# HVAC8New.net
KiCad netlist of a schematic drawn in EAGLE
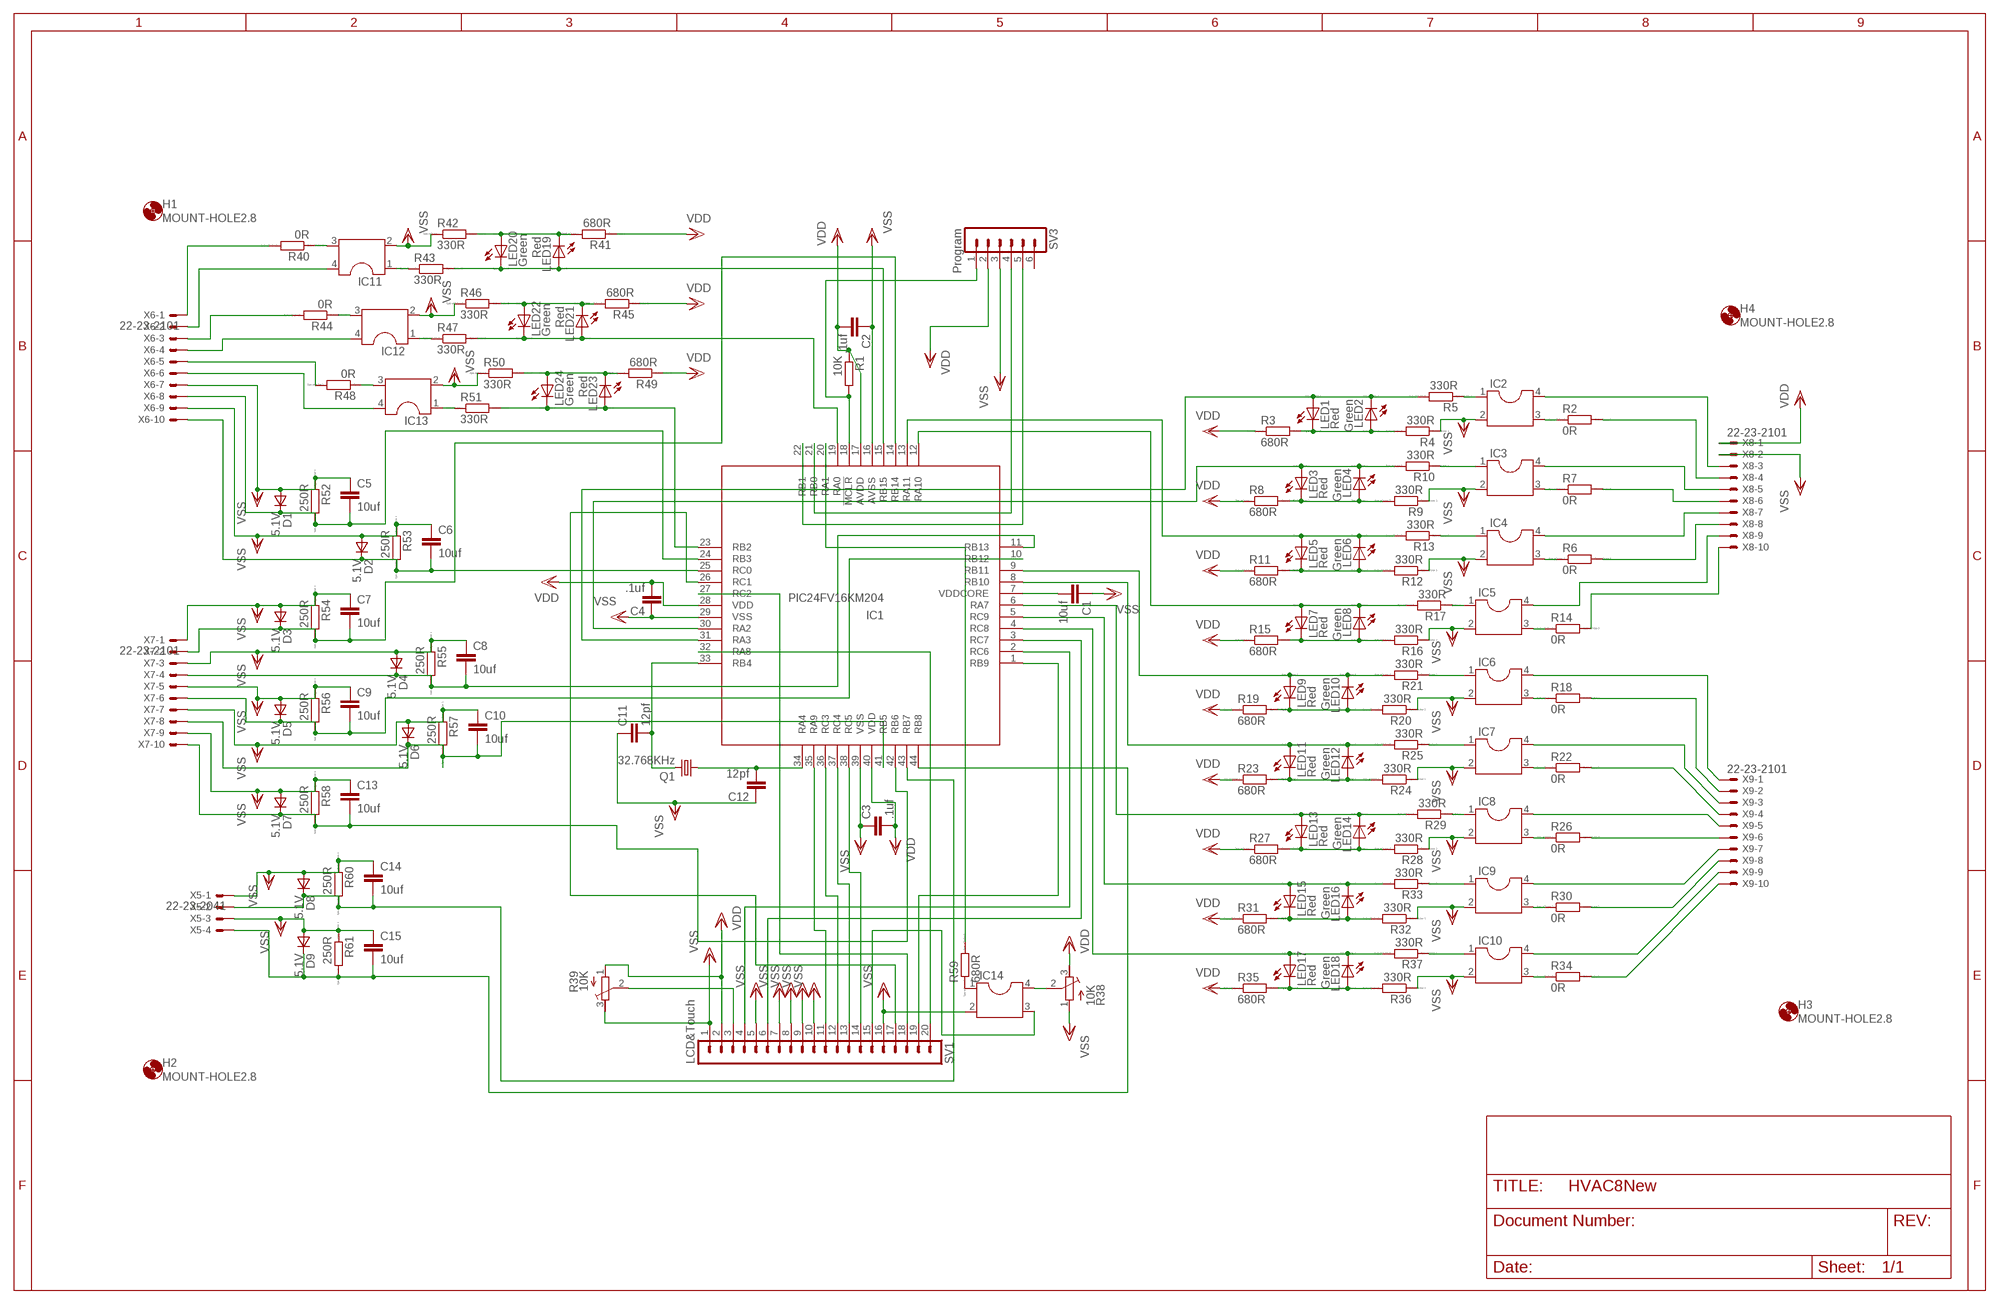
[diagram p0: schematic, sheet 1]

(export (version "E")
  (design (tool "Eeschema 10.0.6"))
  (components
    (comp (ref "C1")
      (value "10uf")
      (footprint "eagle-import:C1206")
      (libsource (lib "eagle-import") (part "C-EUC1206"))
    )
    (comp (ref "C2")
      (value ".1uf")
      (footprint "eagle-import:C1206")
      (libsource (lib "eagle-import") (part "C-EUC1206"))
    )
    (comp (ref "C3")
      (value ".1uf")
      (footprint "eagle-import:C1206")
      (libsource (lib "eagle-import") (part "C-EUC1206"))
    )
    (comp (ref "C4")
      (value ".1uf")
      (footprint "eagle-import:C1206")
      (libsource (lib "eagle-import") (part "C-EUC1206"))
    )
    (comp (ref "C5")
      (value "10uf")
      (footprint "eagle-import:C1206")
      (libsource (lib "eagle-import") (part "C-EUC1206"))
    )
    (comp (ref "C6")
      (value "10uf")
      (footprint "eagle-import:C1206")
      (libsource (lib "eagle-import") (part "C-EUC1206"))
    )
    (comp (ref "C7")
      (value "10uf")
      (footprint "eagle-import:C1206")
      (libsource (lib "eagle-import") (part "C-EUC1206"))
    )
    (comp (ref "C8")
      (value "10uf")
      (footprint "eagle-import:C1206")
      (libsource (lib "eagle-import") (part "C-EUC1206"))
    )
    (comp (ref "C9")
      (value "10uf")
      (footprint "eagle-import:C1206")
      (libsource (lib "eagle-import") (part "C-EUC1206"))
    )
    (comp (ref "C10")
      (value "10uf")
      (footprint "eagle-import:C1206")
      (libsource (lib "eagle-import") (part "C-EUC1206"))
    )
    (comp (ref "C11")
      (value "12pf")
      (footprint "eagle-import:C0603")
      (libsource (lib "eagle-import") (part "C-EUC0603"))
    )
    (comp (ref "C12")
      (value "12pf")
      (footprint "eagle-import:C0603")
      (libsource (lib "eagle-import") (part "C-EUC0603"))
    )
    (comp (ref "C13")
      (value "10uf")
      (footprint "eagle-import:C1206")
      (libsource (lib "eagle-import") (part "C-EUC1206"))
    )
    (comp (ref "C14")
      (value "10uf")
      (footprint "eagle-import:C1206")
      (libsource (lib "eagle-import") (part "C-EUC1206"))
    )
    (comp (ref "C15")
      (value "10uf")
      (footprint "eagle-import:C1206")
      (libsource (lib "eagle-import") (part "C-EUC1206"))
    )
    (comp (ref "D1")
      (value "5.1V")
      (footprint "eagle-import:SOD323")
      (fields (field (name "MPN") "CDSOD323-T05C"))
      (libsource (lib "eagle-import") (part "DSOD323"))
    )
    (comp (ref "D2")
      (value "5.1V")
      (footprint "eagle-import:SOD323")
      (fields (field (name "MPN") "CDSOD323-T05C"))
      (libsource (lib "eagle-import") (part "DSOD323"))
    )
    (comp (ref "D3")
      (value "5.1V")
      (footprint "eagle-import:SOD323")
      (fields (field (name "MPN") "CDSOD323-T05C"))
      (libsource (lib "eagle-import") (part "DSOD323"))
    )
    (comp (ref "D4")
      (value "5.1V")
      (footprint "eagle-import:SOD323")
      (fields (field (name "MPN") "CDSOD323-T05C"))
      (libsource (lib "eagle-import") (part "DSOD323"))
    )
    (comp (ref "D5")
      (value "5.1V")
      (footprint "eagle-import:SOD323")
      (fields (field (name "MPN") "CDSOD323-T05C"))
      (libsource (lib "eagle-import") (part "DSOD323"))
    )
    (comp (ref "D6")
      (value "5.1V")
      (footprint "eagle-import:SOD323")
      (fields (field (name "MPN") "CDSOD323-T05C"))
      (libsource (lib "eagle-import") (part "DSOD323"))
    )
    (comp (ref "D7")
      (value "5.1V")
      (footprint "eagle-import:SOD323")
      (fields (field (name "MPN") "CDSOD323-T05C"))
      (libsource (lib "eagle-import") (part "DSOD323"))
    )
    (comp (ref "D8")
      (value "5.1V")
      (footprint "eagle-import:SOD323")
      (fields (field (name "MPN") "CDSOD323-T05C"))
      (libsource (lib "eagle-import") (part "DSOD323"))
    )
    (comp (ref "D9")
      (value "5.1V")
      (footprint "eagle-import:SOD323")
      (fields (field (name "MPN") "CDSOD323-T05C"))
      (libsource (lib "eagle-import") (part "DSOD323"))
    )
    (comp (ref "H1")
      (value "MOUNT-HOLE2.8")
      (footprint "eagle-import:2,8")
      (libsource (lib "eagle-import") (part "MOUNT-HOLE2.8"))
    )
    (comp (ref "H2")
      (value "MOUNT-HOLE2.8")
      (footprint "eagle-import:2,8")
      (libsource (lib "eagle-import") (part "MOUNT-HOLE2.8"))
    )
    (comp (ref "H3")
      (value "MOUNT-HOLE2.8")
      (footprint "eagle-import:2,8")
      (libsource (lib "eagle-import") (part "MOUNT-HOLE2.8"))
    )
    (comp (ref "H4")
      (value "MOUNT-HOLE2.8")
      (footprint "eagle-import:2,8")
      (libsource (lib "eagle-import") (part "MOUNT-HOLE2.8"))
    )
    (comp (ref "IC1")
      (value "PIC24FV16KM204")
      (footprint "eagle-import:TQFP44")
      (libsource (lib "eagle-import") (part "PIC24FV16KM204"))
    )
    (comp (ref "IC2")
      (value "DIL4S")
      (footprint "eagle-import:SOCKET-04")
      (libsource (lib "eagle-import") (part "DIL4S"))
    )
    (comp (ref "IC3")
      (value "DIL4S")
      (footprint "eagle-import:SOCKET-04")
      (libsource (lib "eagle-import") (part "DIL4S"))
    )
    (comp (ref "IC4")
      (value "DIL4S")
      (footprint "eagle-import:SOCKET-04")
      (libsource (lib "eagle-import") (part "DIL4S"))
    )
    (comp (ref "IC5")
      (value "DIL4S")
      (footprint "eagle-import:SOCKET-04")
      (libsource (lib "eagle-import") (part "DIL4S"))
    )
    (comp (ref "IC6")
      (value "DIL4S")
      (footprint "eagle-import:SOCKET-04")
      (libsource (lib "eagle-import") (part "DIL4S"))
    )
    (comp (ref "IC7")
      (value "DIL4S")
      (footprint "eagle-import:SOCKET-04")
      (libsource (lib "eagle-import") (part "DIL4S"))
    )
    (comp (ref "IC8")
      (value "DIL4S")
      (footprint "eagle-import:SOCKET-04")
      (libsource (lib "eagle-import") (part "DIL4S"))
    )
    (comp (ref "IC9")
      (value "DIL4S")
      (footprint "eagle-import:SOCKET-04")
      (libsource (lib "eagle-import") (part "DIL4S"))
    )
    (comp (ref "IC10")
      (value "DIL4S")
      (footprint "eagle-import:SOCKET-04")
      (libsource (lib "eagle-import") (part "DIL4S"))
    )
    (comp (ref "IC11")
      (value "DIL4S")
      (footprint "eagle-import:SOCKET-04")
      (libsource (lib "eagle-import") (part "DIL4S"))
    )
    (comp (ref "IC12")
      (value "DIL4S")
      (footprint "eagle-import:SOCKET-04")
      (libsource (lib "eagle-import") (part "DIL4S"))
    )
    (comp (ref "IC13")
      (value "DIL4S")
      (footprint "eagle-import:SOCKET-04")
      (libsource (lib "eagle-import") (part "DIL4S"))
    )
    (comp (ref "IC14")
      (value "DIL4S")
      (footprint "eagle-import:SOCKET-04")
      (libsource (lib "eagle-import") (part "DIL4S"))
    )
    (comp (ref "LED1")
      (value "Red")
      (footprint "eagle-import:LED_1206")
      (libsource (lib "eagle-import") (part "LED_E"))
    )
    (comp (ref "LED2")
      (value "Green")
      (footprint "eagle-import:LED_1206")
      (libsource (lib "eagle-import") (part "LED_E"))
    )
    (comp (ref "LED3")
      (value "Red")
      (footprint "eagle-import:LED_1206")
      (libsource (lib "eagle-import") (part "LED_E"))
    )
    (comp (ref "LED4")
      (value "Green")
      (footprint "eagle-import:LED_1206")
      (libsource (lib "eagle-import") (part "LED_E"))
    )
    (comp (ref "LED5")
      (value "Red")
      (footprint "eagle-import:LED_1206")
      (libsource (lib "eagle-import") (part "LED_E"))
    )
    (comp (ref "LED6")
      (value "Green")
      (footprint "eagle-import:LED_1206")
      (libsource (lib "eagle-import") (part "LED_E"))
    )
    (comp (ref "LED7")
      (value "Red")
      (footprint "eagle-import:LED_1206")
      (libsource (lib "eagle-import") (part "LED_E"))
    )
    (comp (ref "LED8")
      (value "Green")
      (footprint "eagle-import:LED_1206")
      (libsource (lib "eagle-import") (part "LED_E"))
    )
    (comp (ref "LED9")
      (value "Red")
      (footprint "eagle-import:LED_1206")
      (libsource (lib "eagle-import") (part "LED_E"))
    )
    (comp (ref "LED10")
      (value "Green")
      (footprint "eagle-import:LED_1206")
      (libsource (lib "eagle-import") (part "LED_E"))
    )
    (comp (ref "LED11")
      (value "Red")
      (footprint "eagle-import:LED_1206")
      (libsource (lib "eagle-import") (part "LED_E"))
    )
    (comp (ref "LED12")
      (value "Green")
      (footprint "eagle-import:LED_1206")
      (libsource (lib "eagle-import") (part "LED_E"))
    )
    (comp (ref "LED13")
      (value "Red")
      (footprint "eagle-import:LED_1206")
      (libsource (lib "eagle-import") (part "LED_E"))
    )
    (comp (ref "LED14")
      (value "Green")
      (footprint "eagle-import:LED_1206")
      (libsource (lib "eagle-import") (part "LED_E"))
    )
    (comp (ref "LED15")
      (value "Red")
      (footprint "eagle-import:LED_1206")
      (libsource (lib "eagle-import") (part "LED_E"))
    )
    (comp (ref "LED16")
      (value "Green")
      (footprint "eagle-import:LED_1206")
      (libsource (lib "eagle-import") (part "LED_E"))
    )
    (comp (ref "LED17")
      (value "Red")
      (footprint "eagle-import:LED_1206")
      (libsource (lib "eagle-import") (part "LED_E"))
    )
    (comp (ref "LED18")
      (value "Green")
      (footprint "eagle-import:LED_1206")
      (libsource (lib "eagle-import") (part "LED_E"))
    )
    (comp (ref "LED19")
      (value "Red")
      (footprint "eagle-import:LED_1206")
      (libsource (lib "eagle-import") (part "LED_E"))
    )
    (comp (ref "LED20")
      (value "Green")
      (footprint "eagle-import:LED_1206")
      (libsource (lib "eagle-import") (part "LED_E"))
    )
    (comp (ref "LED21")
      (value "Red")
      (footprint "eagle-import:LED_1206")
      (libsource (lib "eagle-import") (part "LED_E"))
    )
    (comp (ref "LED22")
      (value "Green")
      (footprint "eagle-import:LED_1206")
      (libsource (lib "eagle-import") (part "LED_E"))
    )
    (comp (ref "LED23")
      (value "Red")
      (footprint "eagle-import:LED_1206")
      (libsource (lib "eagle-import") (part "LED_E"))
    )
    (comp (ref "LED24")
      (value "Green")
      (footprint "eagle-import:LED_1206")
      (libsource (lib "eagle-import") (part "LED_E"))
    )
    (comp (ref "Q1")
      (value "32.768KHz")
      (footprint "eagle-import:TC26H")
      (libsource (lib "eagle-import") (part "CRYSTALTC26H"))
    )
    (comp (ref "R1")
      (value "10K")
      (footprint "eagle-import:R1206")
      (libsource (lib "eagle-import") (part "R-EU_R1206"))
    )
    (comp (ref "R2")
      (value "0R")
      (footprint "eagle-import:R1206")
      (libsource (lib "eagle-import") (part "RR1206"))
    )
    (comp (ref "R3")
      (value "680R")
      (footprint "eagle-import:R1206")
      (libsource (lib "eagle-import") (part "RR1206"))
    )
    (comp (ref "R4")
      (value "330R")
      (footprint "eagle-import:R1206")
      (libsource (lib "eagle-import") (part "RR1206"))
    )
    (comp (ref "R5")
      (value "330R")
      (footprint "eagle-import:R1206")
      (libsource (lib "eagle-import") (part "RR1206"))
    )
    (comp (ref "R6")
      (value "0R")
      (footprint "eagle-import:R1206")
      (libsource (lib "eagle-import") (part "RR1206"))
    )
    (comp (ref "R7")
      (value "0R")
      (footprint "eagle-import:R1206")
      (libsource (lib "eagle-import") (part "RR1206"))
    )
    (comp (ref "R8")
      (value "680R")
      (footprint "eagle-import:R1206")
      (libsource (lib "eagle-import") (part "RR1206"))
    )
    (comp (ref "R9")
      (value "330R")
      (footprint "eagle-import:R1206")
      (libsource (lib "eagle-import") (part "RR1206"))
    )
    (comp (ref "R10")
      (value "330R")
      (footprint "eagle-import:R1206")
      (libsource (lib "eagle-import") (part "RR1206"))
    )
    (comp (ref "R11")
      (value "680R")
      (footprint "eagle-import:R1206")
      (libsource (lib "eagle-import") (part "RR1206"))
    )
    (comp (ref "R12")
      (value "330R")
      (footprint "eagle-import:R1206")
      (libsource (lib "eagle-import") (part "RR1206"))
    )
    (comp (ref "R13")
      (value "330R")
      (footprint "eagle-import:R1206")
      (libsource (lib "eagle-import") (part "RR1206"))
    )
    (comp (ref "R14")
      (value "0R")
      (footprint "eagle-import:R1206")
      (libsource (lib "eagle-import") (part "RR1206"))
    )
    (comp (ref "R15")
      (value "680R")
      (footprint "eagle-import:R1206")
      (libsource (lib "eagle-import") (part "RR1206"))
    )
    (comp (ref "R16")
      (value "330R")
      (footprint "eagle-import:R1206")
      (libsource (lib "eagle-import") (part "RR1206"))
    )
    (comp (ref "R17")
      (value "330R")
      (footprint "eagle-import:R1206")
      (libsource (lib "eagle-import") (part "RR1206"))
    )
    (comp (ref "R18")
      (value "0R")
      (footprint "eagle-import:R1206")
      (libsource (lib "eagle-import") (part "RR1206"))
    )
    (comp (ref "R19")
      (value "680R")
      (footprint "eagle-import:R1206")
      (libsource (lib "eagle-import") (part "RR1206"))
    )
    (comp (ref "R20")
      (value "330R")
      (footprint "eagle-import:R1206")
      (libsource (lib "eagle-import") (part "RR1206"))
    )
    (comp (ref "R21")
      (value "330R")
      (footprint "eagle-import:R1206")
      (libsource (lib "eagle-import") (part "RR1206"))
    )
    (comp (ref "R22")
      (value "0R")
      (footprint "eagle-import:R1206")
      (libsource (lib "eagle-import") (part "RR1206"))
    )
    (comp (ref "R23")
      (value "680R")
      (footprint "eagle-import:R1206")
      (libsource (lib "eagle-import") (part "RR1206"))
    )
    (comp (ref "R24")
      (value "330R")
      (footprint "eagle-import:R1206")
      (libsource (lib "eagle-import") (part "RR1206"))
    )
    (comp (ref "R25")
      (value "330R")
      (footprint "eagle-import:R1206")
      (libsource (lib "eagle-import") (part "RR1206"))
    )
    (comp (ref "R26")
      (value "0R")
      (footprint "eagle-import:R1206")
      (libsource (lib "eagle-import") (part "RR1206"))
    )
    (comp (ref "R27")
      (value "680R")
      (footprint "eagle-import:R1206")
      (libsource (lib "eagle-import") (part "RR1206"))
    )
    (comp (ref "R28")
      (value "330R")
      (footprint "eagle-import:R1206")
      (libsource (lib "eagle-import") (part "RR1206"))
    )
    (comp (ref "R29")
      (value "330R")
      (footprint "eagle-import:R1206")
      (libsource (lib "eagle-import") (part "RR1206"))
    )
    (comp (ref "R30")
      (value "0R")
      (footprint "eagle-import:R1206")
      (libsource (lib "eagle-import") (part "RR1206"))
    )
    (comp (ref "R31")
      (value "680R")
      (footprint "eagle-import:R1206")
      (libsource (lib "eagle-import") (part "RR1206"))
    )
    (comp (ref "R32")
      (value "330R")
      (footprint "eagle-import:R1206")
      (libsource (lib "eagle-import") (part "RR1206"))
    )
    (comp (ref "R33")
      (value "330R")
      (footprint "eagle-import:R1206")
      (libsource (lib "eagle-import") (part "RR1206"))
    )
    (comp (ref "R34")
      (value "0R")
      (footprint "eagle-import:R1206")
      (libsource (lib "eagle-import") (part "RR1206"))
    )
    (comp (ref "R35")
      (value "680R")
      (footprint "eagle-import:R1206")
      (libsource (lib "eagle-import") (part "RR1206"))
    )
    (comp (ref "R36")
      (value "330R")
      (footprint "eagle-import:R1206")
      (libsource (lib "eagle-import") (part "RR1206"))
    )
    (comp (ref "R37")
      (value "330R")
      (footprint "eagle-import:R1206")
      (libsource (lib "eagle-import") (part "RR1206"))
    )
    (comp (ref "R38")
      (value "10K")
      (footprint "eagle-import:RTRIM3296W")
      (libsource (lib "eagle-import") (part "R-TRIMM3296W"))
    )
    (comp (ref "R39")
      (value "10K")
      (footprint "eagle-import:RTRIM3296W")
      (libsource (lib "eagle-import") (part "R-TRIMM3296W"))
    )
    (comp (ref "R40")
      (value "0R")
      (footprint "eagle-import:R1206")
      (libsource (lib "eagle-import") (part "RR1206"))
    )
    (comp (ref "R41")
      (value "680R")
      (footprint "eagle-import:R1206")
      (libsource (lib "eagle-import") (part "RR1206"))
    )
    (comp (ref "R42")
      (value "330R")
      (footprint "eagle-import:R1206")
      (libsource (lib "eagle-import") (part "RR1206"))
    )
    (comp (ref "R43")
      (value "330R")
      (footprint "eagle-import:R1206")
      (libsource (lib "eagle-import") (part "RR1206"))
    )
    (comp (ref "R44")
      (value "0R")
      (footprint "eagle-import:R1206")
      (libsource (lib "eagle-import") (part "RR1206"))
    )
    (comp (ref "R45")
      (value "680R")
      (footprint "eagle-import:R1206")
      (libsource (lib "eagle-import") (part "RR1206"))
    )
    (comp (ref "R46")
      (value "330R")
      (footprint "eagle-import:R1206")
      (libsource (lib "eagle-import") (part "RR1206"))
    )
    (comp (ref "R47")
      (value "330R")
      (footprint "eagle-import:R1206")
      (libsource (lib "eagle-import") (part "RR1206"))
    )
    (comp (ref "R48")
      (value "0R")
      (footprint "eagle-import:R1206")
      (libsource (lib "eagle-import") (part "RR1206"))
    )
    (comp (ref "R49")
      (value "680R")
      (footprint "eagle-import:R1206")
      (libsource (lib "eagle-import") (part "RR1206"))
    )
    (comp (ref "R50")
      (value "330R")
      (footprint "eagle-import:R1206")
      (libsource (lib "eagle-import") (part "RR1206"))
    )
    (comp (ref "R51")
      (value "330R")
      (footprint "eagle-import:R1206")
      (libsource (lib "eagle-import") (part "RR1206"))
    )
    (comp (ref "R52")
      (value "250R")
      (footprint "eagle-import:R1206")
      (libsource (lib "eagle-import") (part "RR1206"))
    )
    (comp (ref "R53")
      (value "250R")
      (footprint "eagle-import:R1206")
      (libsource (lib "eagle-import") (part "RR1206"))
    )
    (comp (ref "R54")
      (value "250R")
      (footprint "eagle-import:R1206")
      (libsource (lib "eagle-import") (part "RR1206"))
    )
    (comp (ref "R55")
      (value "250R")
      (footprint "eagle-import:R1206")
      (libsource (lib "eagle-import") (part "RR1206"))
    )
    (comp (ref "R56")
      (value "250R")
      (footprint "eagle-import:R1206")
      (libsource (lib "eagle-import") (part "RR1206"))
    )
    (comp (ref "R57")
      (value "250R")
      (footprint "eagle-import:R1206")
      (libsource (lib "eagle-import") (part "RR1206"))
    )
    (comp (ref "R58")
      (value "250R")
      (footprint "eagle-import:R1206")
      (libsource (lib "eagle-import") (part "RR1206"))
    )
    (comp (ref "R59")
      (value "680R")
      (footprint "eagle-import:R1206")
      (libsource (lib "eagle-import") (part "RR1206"))
    )
    (comp (ref "R60")
      (value "250R")
      (footprint "eagle-import:R1206")
      (libsource (lib "eagle-import") (part "RR1206"))
    )
    (comp (ref "R61")
      (value "250R")
      (footprint "eagle-import:R1206")
      (libsource (lib "eagle-import") (part "RR1206"))
    )
    (comp (ref "SV1")
      (value "LCD&Touch")
      (footprint "eagle-import:MA20-1")
      (libsource (lib "eagle-import") (part "MA20-1"))
    )
    (comp (ref "SV3")
      (value "Program")
      (footprint "eagle-import:MA06-1")
      (libsource (lib "eagle-import") (part "MA06-1"))
    )
    (comp (ref "X5")
      (value "22-23-2041")
      (footprint "eagle-import:22-23-2041")
      (fields (field (name "MF") "MOLEX"))
      (libsource (lib "eagle-import") (part "22-23-2041"))
    )
    (comp (ref "X6")
      (value "22-23-2101")
      (footprint "eagle-import:22-23-2101")
      (fields (field (name "MF") "MOLEX"))
      (libsource (lib "eagle-import") (part "22-23-2101"))
    )
    (comp (ref "X7")
      (value "22-23-2101")
      (footprint "eagle-import:22-23-2101")
      (fields (field (name "MF") "MOLEX"))
      (libsource (lib "eagle-import") (part "22-23-2101"))
    )
    (comp (ref "X8")
      (value "22-23-2101")
      (footprint "eagle-import:22-23-2101")
      (fields (field (name "MF") "MOLEX"))
      (libsource (lib "eagle-import") (part "22-23-2101"))
    )
    (comp (ref "X9")
      (value "22-23-2101")
      (footprint "eagle-import:22-23-2101")
      (fields (field (name "MF") "MOLEX"))
      (libsource (lib "eagle-import") (part "22-23-2101"))
    )
  )
  (nets
    (net (code "1") (name "Net-(D1-C)") (class "Default")
      (node (ref "C5") (pin "2") (pinfunction "2_2") (pintype "passive"))
      (node (ref "D1") (pin "1") (pinfunction "C_1") (pintype "passive"))
      (node (ref "IC1") (pin "24") (pinfunction "RB3_24") (pintype "bidirectional"))
      (node (ref "R52") (pin "2") (pinfunction "2_2") (pintype "passive"))
      (node (ref "X6") (pin "8") (pinfunction "S_8") (pintype "passive"))
    )
    (net (code "2") (name "Net-(D2-C)") (class "Default")
      (node (ref "C6") (pin "2") (pinfunction "2_2") (pintype "passive"))
      (node (ref "D2") (pin "1") (pinfunction "C_1") (pintype "passive"))
      (node (ref "IC1") (pin "25") (pinfunction "RC0_25") (pintype "bidirectional"))
      (node (ref "R53") (pin "2") (pinfunction "2_2") (pintype "passive"))
      (node (ref "X6") (pin "10") (pinfunction "S_10") (pintype "passive"))
    )
    (net (code "3") (name "Net-(D3-C)") (class "Default")
      (node (ref "C7") (pin "2") (pinfunction "2_2") (pintype "passive"))
      (node (ref "D3") (pin "1") (pinfunction "C_1") (pintype "passive"))
      (node (ref "IC1") (pin "14") (pinfunction "RB14_14") (pintype "bidirectional"))
      (node (ref "R54") (pin "2") (pinfunction "2_2") (pintype "passive"))
      (node (ref "X7") (pin "2") (pinfunction "S_2") (pintype "passive"))
    )
    (net (code "4") (name "Net-(D4-C)") (class "Default")
      (node (ref "C8") (pin "2") (pinfunction "2_2") (pintype "passive"))
      (node (ref "D4") (pin "1") (pinfunction "C_1") (pintype "passive"))
      (node (ref "IC1") (pin "11") (pinfunction "RB13_11") (pintype "bidirectional"))
      (node (ref "R55") (pin "2") (pinfunction "2_2") (pintype "passive"))
      (node (ref "X7") (pin "4") (pinfunction "S_4") (pintype "passive"))
    )
    (net (code "5") (name "Net-(D5-C)") (class "Default")
      (node (ref "C9") (pin "2") (pinfunction "2_2") (pintype "passive"))
      (node (ref "D5") (pin "1") (pinfunction "C_1") (pintype "passive"))
      (node (ref "IC1") (pin "10") (pinfunction "RB12_10") (pintype "bidirectional"))
      (node (ref "R56") (pin "2") (pinfunction "2_2") (pintype "passive"))
      (node (ref "X7") (pin "6") (pinfunction "S_6") (pintype "passive"))
    )
    (net (code "6") (name "Net-(D6-C)") (class "Default")
      (node (ref "C10") (pin "2") (pinfunction "2_2") (pintype "passive"))
      (node (ref "D6") (pin "1") (pinfunction "C_1") (pintype "passive"))
      (node (ref "IC1") (pin "41") (pinfunction "RB5_41") (pintype "bidirectional"))
      (node (ref "R57") (pin "2") (pinfunction "2_2") (pintype "passive"))
      (node (ref "X7") (pin "8") (pinfunction "S_8") (pintype "passive"))
    )
    (net (code "7") (name "Net-(D7-C)") (class "Default")
      (node (ref "C13") (pin "2") (pinfunction "2_2") (pintype "passive"))
      (node (ref "D7") (pin "1") (pinfunction "C_1") (pintype "passive"))
      (node (ref "IC1") (pin "42") (pinfunction "RB6_42") (pintype "bidirectional"))
      (node (ref "R58") (pin "2") (pinfunction "2_2") (pintype "passive"))
      (node (ref "X7") (pin "10") (pinfunction "S_10") (pintype "passive"))
    )
    (net (code "8") (name "Net-(D8-C)") (class "Default")
      (node (ref "C14") (pin "2") (pinfunction "2_2") (pintype "passive"))
      (node (ref "D8") (pin "1") (pinfunction "C_1") (pintype "passive"))
      (node (ref "IC1") (pin "43") (pinfunction "RB7_43") (pintype "bidirectional"))
      (node (ref "R60") (pin "2") (pinfunction "2_2") (pintype "passive"))
      (node (ref "X5") (pin "2") (pinfunction "S_2") (pintype "passive"))
    )
    (net (code "9") (name "Net-(D9-C)") (class "Default")
      (node (ref "C15") (pin "2") (pinfunction "2_2") (pintype "passive"))
      (node (ref "D9") (pin "1") (pinfunction "C_1") (pintype "passive"))
      (node (ref "IC1") (pin "44") (pinfunction "RB8_44") (pintype "bidirectional"))
      (node (ref "R61") (pin "2") (pinfunction "2_2") (pintype "passive"))
      (node (ref "X5") (pin "4") (pinfunction "S_4") (pintype "passive"))
    )
    (net (code "10") (name "Net-(IC1-RA0)") (class "Default")
      (node (ref "IC1") (pin "19") (pinfunction "RA0_19") (pintype "bidirectional"))
      (node (ref "LED21") (pin "A") (pinfunction "A_A") (pintype "passive"))
      (node (ref "LED22") (pin "C") (pinfunction "C_C") (pintype "passive"))
      (node (ref "R47") (pin "2") (pinfunction "2_2") (pintype "passive"))
    )
    (net (code "11") (name "Net-(IC1-RA1)") (class "Default")
      (node (ref "IC1") (pin "20") (pinfunction "RA1_20") (pintype "bidirectional"))
      (node (ref "R59") (pin "2") (pinfunction "2_2") (pintype "passive"))
    )
    (net (code "12") (name "Net-(IC1-RA2)") (class "Default")
      (node (ref "IC1") (pin "30") (pinfunction "RA2_30") (pintype "bidirectional"))
      (node (ref "LED3") (pin "A") (pinfunction "A_A") (pintype "passive"))
      (node (ref "LED4") (pin "C") (pinfunction "C_C") (pintype "passive"))
      (node (ref "R10") (pin "2") (pinfunction "2_2") (pintype "passive"))
    )
    (net (code "13") (name "Net-(IC1-RA3)") (class "Default")
      (node (ref "IC1") (pin "31") (pinfunction "RA3_31") (pintype "bidirectional"))
      (node (ref "LED1") (pin "A") (pinfunction "A_A") (pintype "passive"))
      (node (ref "LED2") (pin "C") (pinfunction "C_C") (pintype "passive"))
      (node (ref "R5") (pin "2") (pinfunction "2_2") (pintype "passive"))
    )
    (net (code "14") (name "Net-(IC1-RA4)") (class "Default")
      (node (ref "C12") (pin "2") (pinfunction "2_2") (pintype "passive"))
      (node (ref "IC1") (pin "34") (pinfunction "RA4_34") (pintype "bidirectional"))
      (node (ref "Q1") (pin "1") (pinfunction "1_1") (pintype "passive"))
    )
    (net (code "15") (name "Net-(IC1-RA7)") (class "Default")
      (node (ref "IC1") (pin "6") (pinfunction "RA7_6") (pintype "bidirectional"))
      (node (ref "LED13") (pin "A") (pinfunction "A_A") (pintype "passive"))
      (node (ref "LED14") (pin "C") (pinfunction "C_C") (pintype "passive"))
      (node (ref "R29") (pin "2") (pinfunction "2_2") (pintype "passive"))
    )
    (net (code "16") (name "Net-(IC1-RA8)") (class "Default")
      (node (ref "IC1") (pin "32") (pinfunction "RA8_32") (pintype "bidirectional"))
      (node (ref "SV1") (pin "20") (pinfunction "20_20") (pintype "passive"))
    )
    (net (code "17") (name "Net-(IC1-RA9)") (class "Default")
      (node (ref "IC1") (pin "35") (pinfunction "RA9_35") (pintype "bidirectional"))
      (node (ref "SV1") (pin "11") (pinfunction "11_11") (pintype "passive"))
    )
    (net (code "18") (name "Net-(IC1-RA10)") (class "Default")
      (node (ref "IC1") (pin "12") (pinfunction "RA10_12") (pintype "bidirectional"))
      (node (ref "LED7") (pin "A") (pinfunction "A_A") (pintype "passive"))
      (node (ref "LED8") (pin "C") (pinfunction "C_C") (pintype "passive"))
      (node (ref "R17") (pin "2") (pinfunction "2_2") (pintype "passive"))
    )
    (net (code "19") (name "Net-(IC1-RA11)") (class "Default")
      (node (ref "IC1") (pin "13") (pinfunction "RA11_13") (pintype "bidirectional"))
      (node (ref "LED5") (pin "A") (pinfunction "A_A") (pintype "passive"))
      (node (ref "LED6") (pin "C") (pinfunction "C_C") (pintype "passive"))
      (node (ref "R13") (pin "2") (pinfunction "2_2") (pintype "passive"))
    )
    (net (code "20") (name "Net-(IC1-RB0)") (class "Default")
      (node (ref "IC1") (pin "21") (pinfunction "RB0_21") (pintype "bidirectional"))
      (node (ref "SV3") (pin "4") (pinfunction "4_4") (pintype "passive"))
    )
    (net (code "21") (name "Net-(IC1-RB1)") (class "Default")
      (node (ref "IC1") (pin "22") (pinfunction "RB1_22") (pintype "bidirectional"))
      (node (ref "SV3") (pin "5") (pinfunction "5_5") (pintype "passive"))
    )
    (net (code "22") (name "Net-(IC1-RB2)") (class "Default")
      (node (ref "IC1") (pin "23") (pinfunction "RB2_23") (pintype "bidirectional"))
      (node (ref "LED23") (pin "A") (pinfunction "A_A") (pintype "passive"))
      (node (ref "LED24") (pin "C") (pinfunction "C_C") (pintype "passive"))
      (node (ref "R51") (pin "2") (pinfunction "2_2") (pintype "passive"))
    )
    (net (code "23") (name "Net-(IC1-RB4)") (class "Default")
      (node (ref "C11") (pin "2") (pinfunction "2_2") (pintype "passive"))
      (node (ref "IC1") (pin "33") (pinfunction "RB4_33") (pintype "bidirectional"))
      (node (ref "Q1") (pin "2") (pinfunction "2_2") (pintype "passive"))
    )
    (net (code "24") (name "Net-(IC1-RB9)") (class "Default")
      (node (ref "IC1") (pin "1") (pinfunction "RB9_1") (pintype "bidirectional"))
      (node (ref "SV1") (pin "19") (pinfunction "19_19") (pintype "passive"))
    )
    (net (code "25") (name "Net-(IC1-RB10)") (class "Default")
      (node (ref "IC1") (pin "8") (pinfunction "RB10_8") (pintype "bidirectional"))
      (node (ref "LED11") (pin "A") (pinfunction "A_A") (pintype "passive"))
      (node (ref "LED12") (pin "C") (pinfunction "C_C") (pintype "passive"))
      (node (ref "R25") (pin "2") (pinfunction "2_2") (pintype "passive"))
    )
    (net (code "26") (name "Net-(IC1-RB11)") (class "Default")
      (node (ref "IC1") (pin "9") (pinfunction "RB11_9") (pintype "bidirectional"))
      (node (ref "LED10") (pin "C") (pinfunction "C_C") (pintype "passive"))
      (node (ref "LED9") (pin "A") (pinfunction "A_A") (pintype "passive"))
      (node (ref "R21") (pin "2") (pinfunction "2_2") (pintype "passive"))
    )
    (net (code "27") (name "Net-(IC1-RB15)") (class "Default")
      (node (ref "IC1") (pin "15") (pinfunction "RB15_15") (pintype "bidirectional"))
      (node (ref "LED19") (pin "A") (pinfunction "A_A") (pintype "passive"))
      (node (ref "LED20") (pin "C") (pinfunction "C_C") (pintype "passive"))
      (node (ref "R43") (pin "2") (pinfunction "2_2") (pintype "passive"))
    )
    (net (code "28") (name "Net-(IC1-RC1)") (class "Default")
      (node (ref "IC1") (pin "26") (pinfunction "RC1_26") (pintype "bidirectional"))
      (node (ref "SV1") (pin "17") (pinfunction "17_17") (pintype "passive"))
    )
    (net (code "29") (name "Net-(IC1-RC2)") (class "Default")
      (node (ref "IC1") (pin "27") (pinfunction "RC2_27") (pintype "bidirectional"))
      (node (ref "SV1") (pin "18") (pinfunction "18_18") (pintype "passive"))
    )
    (net (code "30") (name "Net-(IC1-RC3)") (class "Default")
      (node (ref "IC1") (pin "36") (pinfunction "RC3_36") (pintype "bidirectional"))
      (node (ref "SV1") (pin "12") (pinfunction "12_12") (pintype "passive"))
    )
    (net (code "31") (name "Net-(IC1-RC4)") (class "Default")
      (node (ref "IC1") (pin "37") (pinfunction "RC4_37") (pintype "bidirectional"))
      (node (ref "SV1") (pin "13") (pinfunction "13_13") (pintype "passive"))
    )
    (net (code "32") (name "Net-(IC1-RC5)") (class "Default")
      (node (ref "IC1") (pin "38") (pinfunction "RC5_38") (pintype "bidirectional"))
      (node (ref "SV1") (pin "14") (pinfunction "14_14") (pintype "passive"))
    )
    (net (code "33") (name "Net-(IC1-RC6)") (class "Default")
      (node (ref "IC1") (pin "2") (pinfunction "RC6_2") (pintype "bidirectional"))
      (node (ref "SV1") (pin "4") (pinfunction "4_4") (pintype "passive"))
    )
    (net (code "34") (name "Net-(IC1-RC7)") (class "Default")
      (node (ref "IC1") (pin "3") (pinfunction "RC7_3") (pintype "bidirectional"))
      (node (ref "SV1") (pin "6") (pinfunction "6_6") (pintype "passive"))
    )
    (net (code "35") (name "Net-(IC1-RC8)") (class "Default")
      (node (ref "IC1") (pin "4") (pinfunction "RC8_4") (pintype "bidirectional"))
      (node (ref "LED17") (pin "A") (pinfunction "A_A") (pintype "passive"))
      (node (ref "LED18") (pin "C") (pinfunction "C_C") (pintype "passive"))
      (node (ref "R37") (pin "2") (pinfunction "2_2") (pintype "passive"))
    )
    (net (code "36") (name "Net-(IC1-RC9)") (class "Default")
      (node (ref "IC1") (pin "5") (pinfunction "RC9_5") (pintype "bidirectional"))
      (node (ref "LED15") (pin "A") (pinfunction "A_A") (pintype "passive"))
      (node (ref "LED16") (pin "C") (pinfunction "C_C") (pintype "passive"))
      (node (ref "R33") (pin "2") (pinfunction "2_2") (pintype "passive"))
    )
    (net (code "37") (name "Net-(IC1-VDDCORE)") (class "Default")
      (node (ref "C1") (pin "2") (pinfunction "2_2") (pintype "passive"))
      (node (ref "IC1") (pin "7") (pinfunction "VDDCORE_7") (pintype "power_in"))
    )
    (net (code "38") (name "Net-(IC1-~{MCLR})") (class "Default")
      (node (ref "IC1") (pin "18") (pinfunction "~{MCLR}_18") (pintype "bidirectional"))
      (node (ref "R1") (pin "2") (pinfunction "2_2") (pintype "passive"))
      (node (ref "SV3") (pin "1") (pinfunction "1_1") (pintype "passive"))
    )
    (net (code "39") (name "Net-(IC2-Pad1)") (class "Default")
      (node (ref "IC2") (pin "1") (pinfunction "1_1") (pintype "passive"))
      (node (ref "R5") (pin "1") (pinfunction "1_1") (pintype "passive"))
    )
    (net (code "40") (name "Net-(IC2-Pad3)") (class "Default")
      (node (ref "IC2") (pin "3") (pinfunction "3_3") (pintype "passive"))
      (node (ref "R2") (pin "1") (pinfunction "1_1") (pintype "passive"))
    )
    (net (code "41") (name "Net-(IC3-Pad1)") (class "Default")
      (node (ref "IC3") (pin "1") (pinfunction "1_1") (pintype "passive"))
      (node (ref "R10") (pin "1") (pinfunction "1_1") (pintype "passive"))
    )
    (net (code "42") (name "Net-(IC3-Pad3)") (class "Default")
      (node (ref "IC3") (pin "3") (pinfunction "3_3") (pintype "passive"))
      (node (ref "R7") (pin "1") (pinfunction "1_1") (pintype "passive"))
    )
    (net (code "43") (name "Net-(IC4-Pad1)") (class "Default")
      (node (ref "IC4") (pin "1") (pinfunction "1_1") (pintype "passive"))
      (node (ref "R13") (pin "1") (pinfunction "1_1") (pintype "passive"))
    )
    (net (code "44") (name "Net-(IC4-Pad3)") (class "Default")
      (node (ref "IC4") (pin "3") (pinfunction "3_3") (pintype "passive"))
      (node (ref "R6") (pin "1") (pinfunction "1_1") (pintype "passive"))
    )
    (net (code "45") (name "Net-(IC5-Pad1)") (class "Default")
      (node (ref "IC5") (pin "1") (pinfunction "1_1") (pintype "passive"))
      (node (ref "R17") (pin "1") (pinfunction "1_1") (pintype "passive"))
    )
    (net (code "46") (name "Net-(IC5-Pad3)") (class "Default")
      (node (ref "IC5") (pin "3") (pinfunction "3_3") (pintype "passive"))
      (node (ref "R14") (pin "1") (pinfunction "1_1") (pintype "passive"))
    )
    (net (code "47") (name "Net-(IC6-Pad1)") (class "Default")
      (node (ref "IC6") (pin "1") (pinfunction "1_1") (pintype "passive"))
      (node (ref "R21") (pin "1") (pinfunction "1_1") (pintype "passive"))
    )
    (net (code "48") (name "Net-(IC6-Pad3)") (class "Default")
      (node (ref "IC6") (pin "3") (pinfunction "3_3") (pintype "passive"))
      (node (ref "R18") (pin "1") (pinfunction "1_1") (pintype "passive"))
    )
    (net (code "49") (name "Net-(IC7-Pad1)") (class "Default")
      (node (ref "IC7") (pin "1") (pinfunction "1_1") (pintype "passive"))
      (node (ref "R25") (pin "1") (pinfunction "1_1") (pintype "passive"))
    )
    (net (code "50") (name "Net-(IC7-Pad3)") (class "Default")
      (node (ref "IC7") (pin "3") (pinfunction "3_3") (pintype "passive"))
      (node (ref "R22") (pin "1") (pinfunction "1_1") (pintype "passive"))
    )
    (net (code "51") (name "Net-(IC8-Pad1)") (class "Default")
      (node (ref "IC8") (pin "1") (pinfunction "1_1") (pintype "passive"))
      (node (ref "R29") (pin "1") (pinfunction "1_1") (pintype "passive"))
    )
    (net (code "52") (name "Net-(IC8-Pad3)") (class "Default")
      (node (ref "IC8") (pin "3") (pinfunction "3_3") (pintype "passive"))
      (node (ref "R26") (pin "1") (pinfunction "1_1") (pintype "passive"))
    )
    (net (code "53") (name "Net-(IC9-Pad1)") (class "Default")
      (node (ref "IC9") (pin "1") (pinfunction "1_1") (pintype "passive"))
      (node (ref "R33") (pin "1") (pinfunction "1_1") (pintype "passive"))
    )
    (net (code "54") (name "Net-(IC9-Pad3)") (class "Default")
      (node (ref "IC9") (pin "3") (pinfunction "3_3") (pintype "passive"))
      (node (ref "R30") (pin "1") (pinfunction "1_1") (pintype "passive"))
    )
    (net (code "55") (name "Net-(IC10-Pad1)") (class "Default")
      (node (ref "IC10") (pin "1") (pinfunction "1_1") (pintype "passive"))
      (node (ref "R37") (pin "1") (pinfunction "1_1") (pintype "passive"))
    )
    (net (code "56") (name "Net-(IC10-Pad3)") (class "Default")
      (node (ref "IC10") (pin "3") (pinfunction "3_3") (pintype "passive"))
      (node (ref "R34") (pin "1") (pinfunction "1_1") (pintype "passive"))
    )
    (net (code "57") (name "Net-(IC11-Pad1)") (class "Default")
      (node (ref "IC11") (pin "1") (pinfunction "1_1") (pintype "passive"))
      (node (ref "R43") (pin "1") (pinfunction "1_1") (pintype "passive"))
    )
    (net (code "58") (name "Net-(IC11-Pad3)") (class "Default")
      (node (ref "IC11") (pin "3") (pinfunction "3_3") (pintype "passive"))
      (node (ref "R40") (pin "1") (pinfunction "1_1") (pintype "passive"))
    )
    (net (code "59") (name "Net-(IC12-Pad1)") (class "Default")
      (node (ref "IC12") (pin "1") (pinfunction "1_1") (pintype "passive"))
      (node (ref "R47") (pin "1") (pinfunction "1_1") (pintype "passive"))
    )
    (net (code "60") (name "Net-(IC12-Pad3)") (class "Default")
      (node (ref "IC12") (pin "3") (pinfunction "3_3") (pintype "passive"))
      (node (ref "R44") (pin "1") (pinfunction "1_1") (pintype "passive"))
    )
    (net (code "61") (name "Net-(IC13-Pad1)") (class "Default")
      (node (ref "IC13") (pin "1") (pinfunction "1_1") (pintype "passive"))
      (node (ref "R51") (pin "1") (pinfunction "1_1") (pintype "passive"))
    )
    (net (code "62") (name "Net-(IC13-Pad3)") (class "Default")
      (node (ref "IC13") (pin "3") (pinfunction "3_3") (pintype "passive"))
      (node (ref "R48") (pin "1") (pinfunction "1_1") (pintype "passive"))
    )
    (net (code "63") (name "Net-(IC14-Pad1)") (class "Default")
      (node (ref "IC14") (pin "1") (pinfunction "1_1") (pintype "passive"))
      (node (ref "R59") (pin "1") (pinfunction "1_1") (pintype "passive"))
    )
    (net (code "64") (name "Net-(IC14-Pad3)") (class "Default")
      (node (ref "IC14") (pin "3") (pinfunction "3_3") (pintype "passive"))
      (node (ref "SV1") (pin "15") (pinfunction "15_15") (pintype "passive"))
    )
    (net (code "65") (name "Net-(LED1-PadC)") (class "Default")
      (node (ref "LED1") (pin "C") (pinfunction "C_C") (pintype "passive"))
      (node (ref "LED2") (pin "A") (pinfunction "A_A") (pintype "passive"))
      (node (ref "R3") (pin "2") (pinfunction "2_2") (pintype "passive"))
      (node (ref "R4") (pin "2") (pinfunction "2_2") (pintype "passive"))
    )
    (net (code "66") (name "Net-(LED3-PadC)") (class "Default")
      (node (ref "LED3") (pin "C") (pinfunction "C_C") (pintype "passive"))
      (node (ref "LED4") (pin "A") (pinfunction "A_A") (pintype "passive"))
      (node (ref "R8") (pin "2") (pinfunction "2_2") (pintype "passive"))
      (node (ref "R9") (pin "2") (pinfunction "2_2") (pintype "passive"))
    )
    (net (code "67") (name "Net-(LED5-PadC)") (class "Default")
      (node (ref "LED5") (pin "C") (pinfunction "C_C") (pintype "passive"))
      (node (ref "LED6") (pin "A") (pinfunction "A_A") (pintype "passive"))
      (node (ref "R11") (pin "2") (pinfunction "2_2") (pintype "passive"))
      (node (ref "R12") (pin "2") (pinfunction "2_2") (pintype "passive"))
    )
    (net (code "68") (name "Net-(LED7-PadC)") (class "Default")
      (node (ref "LED7") (pin "C") (pinfunction "C_C") (pintype "passive"))
      (node (ref "LED8") (pin "A") (pinfunction "A_A") (pintype "passive"))
      (node (ref "R15") (pin "2") (pinfunction "2_2") (pintype "passive"))
      (node (ref "R16") (pin "2") (pinfunction "2_2") (pintype "passive"))
    )
    (net (code "69") (name "Net-(LED10-PadA)") (class "Default")
      (node (ref "LED10") (pin "A") (pinfunction "A_A") (pintype "passive"))
      (node (ref "LED9") (pin "C") (pinfunction "C_C") (pintype "passive"))
      (node (ref "R19") (pin "2") (pinfunction "2_2") (pintype "passive"))
      (node (ref "R20") (pin "2") (pinfunction "2_2") (pintype "passive"))
    )
    (net (code "70") (name "Net-(LED11-PadC)") (class "Default")
      (node (ref "LED11") (pin "C") (pinfunction "C_C") (pintype "passive"))
      (node (ref "LED12") (pin "A") (pinfunction "A_A") (pintype "passive"))
      (node (ref "R23") (pin "2") (pinfunction "2_2") (pintype "passive"))
      (node (ref "R24") (pin "2") (pinfunction "2_2") (pintype "passive"))
    )
    (net (code "71") (name "Net-(LED13-PadC)") (class "Default")
      (node (ref "LED13") (pin "C") (pinfunction "C_C") (pintype "passive"))
      (node (ref "LED14") (pin "A") (pinfunction "A_A") (pintype "passive"))
      (node (ref "R27") (pin "2") (pinfunction "2_2") (pintype "passive"))
      (node (ref "R28") (pin "2") (pinfunction "2_2") (pintype "passive"))
    )
    (net (code "72") (name "Net-(LED15-PadC)") (class "Default")
      (node (ref "LED15") (pin "C") (pinfunction "C_C") (pintype "passive"))
      (node (ref "LED16") (pin "A") (pinfunction "A_A") (pintype "passive"))
      (node (ref "R31") (pin "2") (pinfunction "2_2") (pintype "passive"))
      (node (ref "R32") (pin "2") (pinfunction "2_2") (pintype "passive"))
    )
    (net (code "73") (name "Net-(LED17-PadC)") (class "Default")
      (node (ref "LED17") (pin "C") (pinfunction "C_C") (pintype "passive"))
      (node (ref "LED18") (pin "A") (pinfunction "A_A") (pintype "passive"))
      (node (ref "R35") (pin "2") (pinfunction "2_2") (pintype "passive"))
      (node (ref "R36") (pin "2") (pinfunction "2_2") (pintype "passive"))
    )
    (net (code "74") (name "Net-(LED19-PadC)") (class "Default")
      (node (ref "LED19") (pin "C") (pinfunction "C_C") (pintype "passive"))
      (node (ref "LED20") (pin "A") (pinfunction "A_A") (pintype "passive"))
      (node (ref "R41") (pin "2") (pinfunction "2_2") (pintype "passive"))
      (node (ref "R42") (pin "2") (pinfunction "2_2") (pintype "passive"))
    )
    (net (code "75") (name "Net-(LED21-PadC)") (class "Default")
      (node (ref "LED21") (pin "C") (pinfunction "C_C") (pintype "passive"))
      (node (ref "LED22") (pin "A") (pinfunction "A_A") (pintype "passive"))
      (node (ref "R45") (pin "2") (pinfunction "2_2") (pintype "passive"))
      (node (ref "R46") (pin "2") (pinfunction "2_2") (pintype "passive"))
    )
    (net (code "76") (name "Net-(LED23-PadC)") (class "Default")
      (node (ref "LED23") (pin "C") (pinfunction "C_C") (pintype "passive"))
      (node (ref "LED24") (pin "A") (pinfunction "A_A") (pintype "passive"))
      (node (ref "R49") (pin "2") (pinfunction "2_2") (pintype "passive"))
      (node (ref "R50") (pin "2") (pinfunction "2_2") (pintype "passive"))
    )
    (net (code "77") (name "Net-(R38-S)") (class "Default")
      (node (ref "IC14") (pin "4") (pinfunction "4_4") (pintype "passive"))
      (node (ref "R38") (pin "2") (pinfunction "S_2") (pintype "passive"))
    )
    (net (code "78") (name "Net-(R39-S)") (class "Default")
      (node (ref "R39") (pin "2") (pinfunction "S_2") (pintype "passive"))
      (node (ref "SV1") (pin "3") (pinfunction "3_3") (pintype "passive"))
    )
    (net (code "79") (name "Net-(X6A-S)") (class "Default")
      (node (ref "R40") (pin "2") (pinfunction "2_2") (pintype "passive"))
      (node (ref "X6") (pin "1") (pinfunction "S_1") (pintype "passive"))
    )
    (net (code "80") (name "Net-(X6C-S)") (class "Default")
      (node (ref "IC11") (pin "4") (pinfunction "4_4") (pintype "passive"))
      (node (ref "X6") (pin "2") (pinfunction "S_2") (pintype "passive"))
    )
    (net (code "81") (name "Net-(X6D-S)") (class "Default")
      (node (ref "R44") (pin "2") (pinfunction "2_2") (pintype "passive"))
      (node (ref "X6") (pin "3") (pinfunction "S_3") (pintype "passive"))
    )
    (net (code "82") (name "Net-(X6E-S)") (class "Default")
      (node (ref "IC12") (pin "4") (pinfunction "4_4") (pintype "passive"))
      (node (ref "X6") (pin "4") (pinfunction "S_4") (pintype "passive"))
    )
    (net (code "83") (name "Net-(X6F-S)") (class "Default")
      (node (ref "R48") (pin "2") (pinfunction "2_2") (pintype "passive"))
      (node (ref "X6") (pin "5") (pinfunction "S_5") (pintype "passive"))
    )
    (net (code "84") (name "Net-(X6G-S)") (class "Default")
      (node (ref "IC13") (pin "4") (pinfunction "4_4") (pintype "passive"))
      (node (ref "X6") (pin "6") (pinfunction "S_6") (pintype "passive"))
    )
    (net (code "85") (name "Net-(X8B-S)") (class "Default")
      (node (ref "R14") (pin "2") (pinfunction "2_2") (pintype "passive"))
      (node (ref "X8") (pin "10") (pinfunction "S_10") (pintype "passive"))
    )
    (net (code "86") (name "Net-(X8D-S)") (class "Default")
      (node (ref "IC2") (pin "4") (pinfunction "4_4") (pintype "passive"))
      (node (ref "X8") (pin "3") (pinfunction "S_3") (pintype "passive"))
    )
    (net (code "87") (name "Net-(X8E-S)") (class "Default")
      (node (ref "R2") (pin "2") (pinfunction "2_2") (pintype "passive"))
      (node (ref "X8") (pin "4") (pinfunction "S_4") (pintype "passive"))
    )
    (net (code "88") (name "Net-(X8F-S)") (class "Default")
      (node (ref "IC3") (pin "4") (pinfunction "4_4") (pintype "passive"))
      (node (ref "X8") (pin "5") (pinfunction "S_5") (pintype "passive"))
    )
    (net (code "89") (name "Net-(X8G-S)") (class "Default")
      (node (ref "R7") (pin "2") (pinfunction "2_2") (pintype "passive"))
      (node (ref "X8") (pin "6") (pinfunction "S_6") (pintype "passive"))
    )
    (net (code "90") (name "Net-(X8H-S)") (class "Default")
      (node (ref "IC4") (pin "4") (pinfunction "4_4") (pintype "passive"))
      (node (ref "X8") (pin "7") (pinfunction "S_7") (pintype "passive"))
    )
    (net (code "91") (name "Net-(X8I-S)") (class "Default")
      (node (ref "R6") (pin "2") (pinfunction "2_2") (pintype "passive"))
      (node (ref "X8") (pin "8") (pinfunction "S_8") (pintype "passive"))
    )
    (net (code "92") (name "Net-(X8J-S)") (class "Default")
      (node (ref "IC5") (pin "4") (pinfunction "4_4") (pintype "passive"))
      (node (ref "X8") (pin "9") (pinfunction "S_9") (pintype "passive"))
    )
    (net (code "93") (name "Net-(X9A-S)") (class "Default")
      (node (ref "IC6") (pin "4") (pinfunction "4_4") (pintype "passive"))
      (node (ref "X9") (pin "1") (pinfunction "S_1") (pintype "passive"))
    )
    (net (code "94") (name "Net-(X9B-S)") (class "Default")
      (node (ref "R34") (pin "2") (pinfunction "2_2") (pintype "passive"))
      (node (ref "X9") (pin "10") (pinfunction "S_10") (pintype "passive"))
    )
    (net (code "95") (name "Net-(X9C-S)") (class "Default")
      (node (ref "R18") (pin "2") (pinfunction "2_2") (pintype "passive"))
      (node (ref "X9") (pin "2") (pinfunction "S_2") (pintype "passive"))
    )
    (net (code "96") (name "Net-(X9D-S)") (class "Default")
      (node (ref "IC7") (pin "4") (pinfunction "4_4") (pintype "passive"))
      (node (ref "X9") (pin "3") (pinfunction "S_3") (pintype "passive"))
    )
    (net (code "97") (name "Net-(X9E-S)") (class "Default")
      (node (ref "R22") (pin "2") (pinfunction "2_2") (pintype "passive"))
      (node (ref "X9") (pin "4") (pinfunction "S_4") (pintype "passive"))
    )
    (net (code "98") (name "Net-(X9F-S)") (class "Default")
      (node (ref "IC8") (pin "4") (pinfunction "4_4") (pintype "passive"))
      (node (ref "X9") (pin "5") (pinfunction "S_5") (pintype "passive"))
    )
    (net (code "99") (name "Net-(X9G-S)") (class "Default")
      (node (ref "R26") (pin "2") (pinfunction "2_2") (pintype "passive"))
      (node (ref "X9") (pin "6") (pinfunction "S_6") (pintype "passive"))
    )
    (net (code "100") (name "Net-(X9H-S)") (class "Default")
      (node (ref "IC9") (pin "4") (pinfunction "4_4") (pintype "passive"))
      (node (ref "X9") (pin "7") (pinfunction "S_7") (pintype "passive"))
    )
    (net (code "101") (name "Net-(X9I-S)") (class "Default")
      (node (ref "R30") (pin "2") (pinfunction "2_2") (pintype "passive"))
      (node (ref "X9") (pin "8") (pinfunction "S_8") (pintype "passive"))
    )
    (net (code "102") (name "Net-(X9J-S)") (class "Default")
      (node (ref "IC10") (pin "4") (pinfunction "4_4") (pintype "passive"))
      (node (ref "X9") (pin "9") (pinfunction "S_9") (pintype "passive"))
    )
    (net (code "103") (name "VDD") (class "Default")
      (node (ref "C2") (pin "2") (pinfunction "2_2") (pintype "passive"))
      (node (ref "C3") (pin "2") (pinfunction "2_2") (pintype "passive"))
      (node (ref "C4") (pin "2") (pinfunction "2_2") (pintype "passive"))
      (node (ref "IC1") (pin "17") (pinfunction "AVDD_17") (pintype "power_in"))
      (node (ref "IC1") (pin "28") (pinfunction "VDD_28") (pintype "power_in"))
      (node (ref "IC1") (pin "40") (pinfunction "VDD_40") (pintype "power_in"))
      (node (ref "R1") (pin "1") (pinfunction "1_1") (pintype "passive"))
      (node (ref "R11") (pin "1") (pinfunction "1_1") (pintype "passive"))
      (node (ref "R15") (pin "1") (pinfunction "1_1") (pintype "passive"))
      (node (ref "R19") (pin "1") (pinfunction "1_1") (pintype "passive"))
      (node (ref "R23") (pin "1") (pinfunction "1_1") (pintype "passive"))
      (node (ref "R27") (pin "1") (pinfunction "1_1") (pintype "passive"))
      (node (ref "R3") (pin "1") (pinfunction "1_1") (pintype "passive"))
      (node (ref "R31") (pin "1") (pinfunction "1_1") (pintype "passive"))
      (node (ref "R35") (pin "1") (pinfunction "1_1") (pintype "passive"))
      (node (ref "R38") (pin "3") (pinfunction "E_3") (pintype "passive"))
      (node (ref "R39") (pin "1") (pinfunction "A_1") (pintype "passive"))
      (node (ref "R41") (pin "1") (pinfunction "1_1") (pintype "passive"))
      (node (ref "R45") (pin "1") (pinfunction "1_1") (pintype "passive"))
      (node (ref "R49") (pin "1") (pinfunction "1_1") (pintype "passive"))
      (node (ref "R8") (pin "1") (pinfunction "1_1") (pintype "passive"))
      (node (ref "SV1") (pin "2") (pinfunction "2_2") (pintype "passive"))
      (node (ref "SV3") (pin "2") (pinfunction "2_2") (pintype "passive"))
      (node (ref "X8") (pin "1") (pinfunction "S_1") (pintype "passive"))
    )
    (net (code "104") (name "VSS") (class "Default")
      (node (ref "C1") (pin "1") (pinfunction "1_1") (pintype "passive"))
      (node (ref "C10") (pin "1") (pinfunction "1_1") (pintype "passive"))
      (node (ref "C11") (pin "1") (pinfunction "1_1") (pintype "passive"))
      (node (ref "C12") (pin "1") (pinfunction "1_1") (pintype "passive"))
      (node (ref "C13") (pin "1") (pinfunction "1_1") (pintype "passive"))
      (node (ref "C14") (pin "1") (pinfunction "1_1") (pintype "passive"))
      (node (ref "C15") (pin "1") (pinfunction "1_1") (pintype "passive"))
      (node (ref "C2") (pin "1") (pinfunction "1_1") (pintype "passive"))
      (node (ref "C3") (pin "1") (pinfunction "1_1") (pintype "passive"))
      (node (ref "C4") (pin "1") (pinfunction "1_1") (pintype "passive"))
      (node (ref "C5") (pin "1") (pinfunction "1_1") (pintype "passive"))
      (node (ref "C6") (pin "1") (pinfunction "1_1") (pintype "passive"))
      (node (ref "C7") (pin "1") (pinfunction "1_1") (pintype "passive"))
      (node (ref "C8") (pin "1") (pinfunction "1_1") (pintype "passive"))
      (node (ref "C9") (pin "1") (pinfunction "1_1") (pintype "passive"))
      (node (ref "D1") (pin "2") (pinfunction "A_2") (pintype "passive"))
      (node (ref "D2") (pin "2") (pinfunction "A_2") (pintype "passive"))
      (node (ref "D3") (pin "2") (pinfunction "A_2") (pintype "passive"))
      (node (ref "D4") (pin "2") (pinfunction "A_2") (pintype "passive"))
      (node (ref "D5") (pin "2") (pinfunction "A_2") (pintype "passive"))
      (node (ref "D6") (pin "2") (pinfunction "A_2") (pintype "passive"))
      (node (ref "D7") (pin "2") (pinfunction "A_2") (pintype "passive"))
      (node (ref "D8") (pin "2") (pinfunction "A_2") (pintype "passive"))
      (node (ref "D9") (pin "2") (pinfunction "A_2") (pintype "passive"))
      (node (ref "IC1") (pin "16") (pinfunction "AVSS_16") (pintype "power_in"))
      (node (ref "IC1") (pin "29") (pinfunction "VSS_29") (pintype "power_in"))
      (node (ref "IC1") (pin "39") (pinfunction "VSS_39") (pintype "power_in"))
      (node (ref "IC10") (pin "2") (pinfunction "2_2") (pintype "passive"))
      (node (ref "IC11") (pin "2") (pinfunction "2_2") (pintype "passive"))
      (node (ref "IC12") (pin "2") (pinfunction "2_2") (pintype "passive"))
      (node (ref "IC13") (pin "2") (pinfunction "2_2") (pintype "passive"))
      (node (ref "IC14") (pin "2") (pinfunction "2_2") (pintype "passive"))
      (node (ref "IC2") (pin "2") (pinfunction "2_2") (pintype "passive"))
      (node (ref "IC3") (pin "2") (pinfunction "2_2") (pintype "passive"))
      (node (ref "IC4") (pin "2") (pinfunction "2_2") (pintype "passive"))
      (node (ref "IC5") (pin "2") (pinfunction "2_2") (pintype "passive"))
      (node (ref "IC6") (pin "2") (pinfunction "2_2") (pintype "passive"))
      (node (ref "IC7") (pin "2") (pinfunction "2_2") (pintype "passive"))
      (node (ref "IC8") (pin "2") (pinfunction "2_2") (pintype "passive"))
      (node (ref "IC9") (pin "2") (pinfunction "2_2") (pintype "passive"))
      (node (ref "R12") (pin "1") (pinfunction "1_1") (pintype "passive"))
      (node (ref "R16") (pin "1") (pinfunction "1_1") (pintype "passive"))
      (node (ref "R20") (pin "1") (pinfunction "1_1") (pintype "passive"))
      (node (ref "R24") (pin "1") (pinfunction "1_1") (pintype "passive"))
      (node (ref "R28") (pin "1") (pinfunction "1_1") (pintype "passive"))
      (node (ref "R32") (pin "1") (pinfunction "1_1") (pintype "passive"))
      (node (ref "R36") (pin "1") (pinfunction "1_1") (pintype "passive"))
      (node (ref "R38") (pin "1") (pinfunction "A_1") (pintype "passive"))
      (node (ref "R39") (pin "3") (pinfunction "E_3") (pintype "passive"))
      (node (ref "R4") (pin "1") (pinfunction "1_1") (pintype "passive"))
      (node (ref "R42") (pin "1") (pinfunction "1_1") (pintype "passive"))
      (node (ref "R46") (pin "1") (pinfunction "1_1") (pintype "passive"))
      (node (ref "R50") (pin "1") (pinfunction "1_1") (pintype "passive"))
      (node (ref "R52") (pin "1") (pinfunction "1_1") (pintype "passive"))
      (node (ref "R53") (pin "1") (pinfunction "1_1") (pintype "passive"))
      (node (ref "R54") (pin "1") (pinfunction "1_1") (pintype "passive"))
      (node (ref "R55") (pin "1") (pinfunction "1_1") (pintype "passive"))
      (node (ref "R56") (pin "1") (pinfunction "1_1") (pintype "passive"))
      (node (ref "R57") (pin "1") (pinfunction "1_1") (pintype "passive"))
      (node (ref "R58") (pin "1") (pinfunction "1_1") (pintype "passive"))
      (node (ref "R60") (pin "1") (pinfunction "1_1") (pintype "passive"))
      (node (ref "R61") (pin "1") (pinfunction "1_1") (pintype "passive"))
      (node (ref "R9") (pin "1") (pinfunction "1_1") (pintype "passive"))
      (node (ref "SV1") (pin "1") (pinfunction "1_1") (pintype "passive"))
      (node (ref "SV1") (pin "10") (pinfunction "10_10") (pintype "passive"))
      (node (ref "SV1") (pin "16") (pinfunction "16_16") (pintype "passive"))
      (node (ref "SV1") (pin "5") (pinfunction "5_5") (pintype "passive"))
      (node (ref "SV1") (pin "7") (pinfunction "7_7") (pintype "passive"))
      (node (ref "SV1") (pin "8") (pinfunction "8_8") (pintype "passive"))
      (node (ref "SV1") (pin "9") (pinfunction "9_9") (pintype "passive"))
      (node (ref "SV3") (pin "3") (pinfunction "3_3") (pintype "passive"))
      (node (ref "X5") (pin "1") (pinfunction "S_1") (pintype "passive"))
      (node (ref "X5") (pin "3") (pinfunction "S_3") (pintype "passive"))
      (node (ref "X6") (pin "7") (pinfunction "S_7") (pintype "passive"))
      (node (ref "X6") (pin "9") (pinfunction "S_9") (pintype "passive"))
      (node (ref "X7") (pin "1") (pinfunction "S_1") (pintype "passive"))
      (node (ref "X7") (pin "3") (pinfunction "S_3") (pintype "passive"))
      (node (ref "X7") (pin "5") (pinfunction "S_5") (pintype "passive"))
      (node (ref "X7") (pin "7") (pinfunction "S_7") (pintype "passive"))
      (node (ref "X7") (pin "9") (pinfunction "S_9") (pintype "passive"))
      (node (ref "X8") (pin "2") (pinfunction "S_2") (pintype "passive"))
    )
    (net (code "105") (name "unconnected-(SV3-Pad6)") (class "Default")
      (node (ref "SV3") (pin "6") (pinfunction "6_6") (pintype "passive"))
    )
  )
)
